# Schematic.net
KiCad netlist of a schematic drawn in Altium Designer
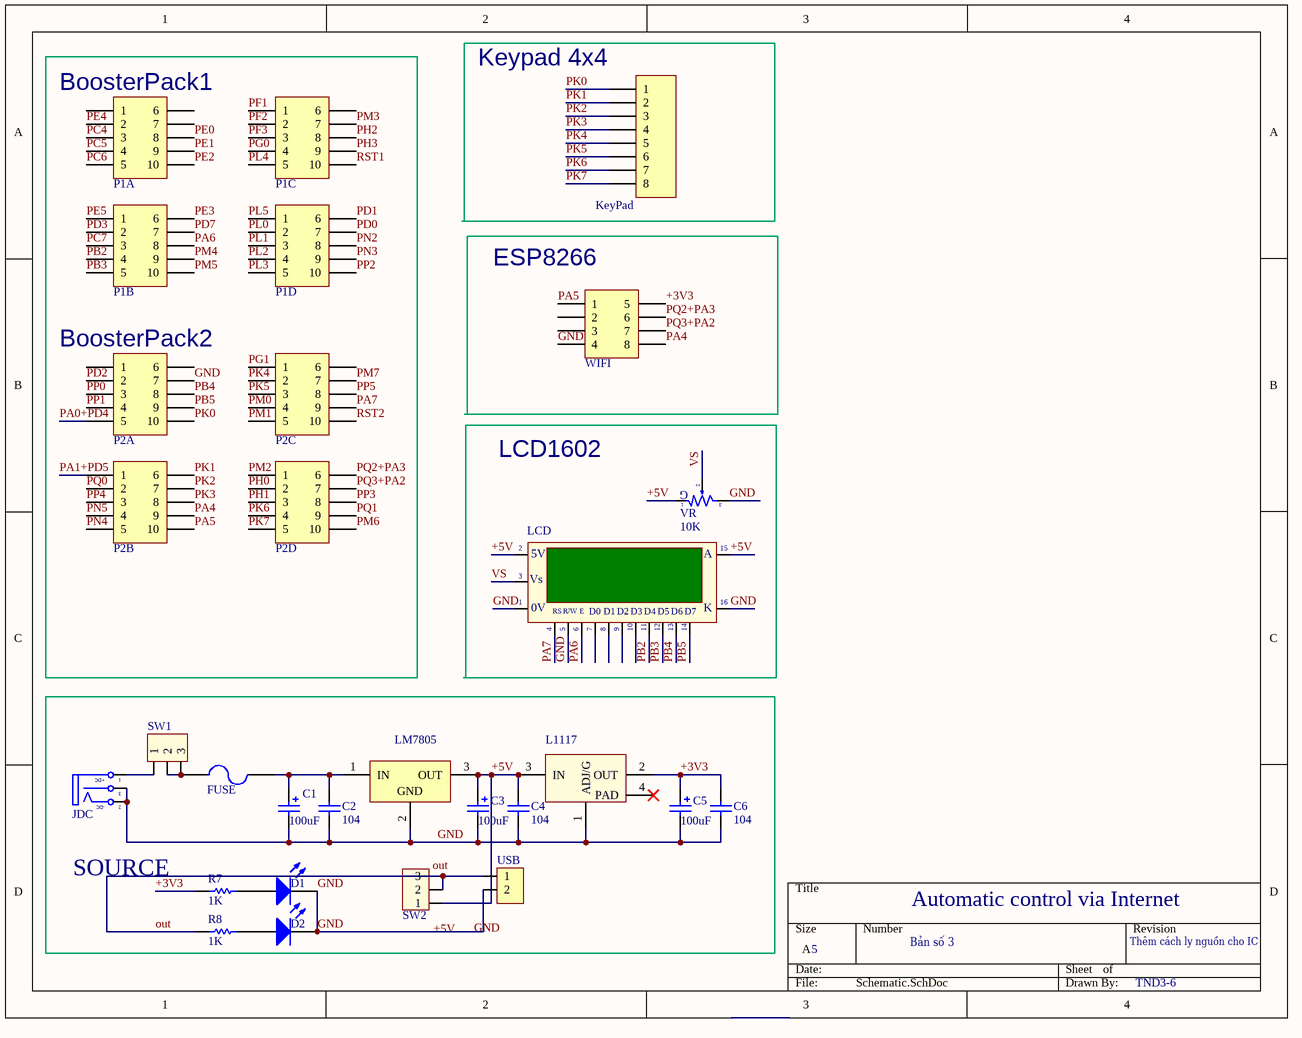
[diagram p0: Schematic.SchDoc]

(export (version "E")
  (design (tool "Eeschema 10.0.6"))
  (components
    (comp (ref "C1")
      (value "100uF")
      (footprint "CP1/2")
      (description "Polarized Capacitor (Radial)")
      (fields (field (name "Comment") "Cap Pol"))
      (libsource (lib "PIF_Library") (part "Cap Pol"))
    )
    (comp (ref "C2")
      (value "104")
      (footprint "CN1")
      (description "Capacitor")
      (fields (field (name "Comment") "Cap Non-Pol"))
      (libsource (lib "PIF_Library") (part "Cap Non-Pol"))
    )
    (comp (ref "C3")
      (value "100uF")
      (footprint "CP1/2")
      (description "Polarized Capacitor (Radial)")
      (fields (field (name "Comment") "Cap Pol"))
      (libsource (lib "PIF_Library") (part "Cap Pol"))
    )
    (comp (ref "C4")
      (value "104")
      (footprint "CN1")
      (description "Capacitor")
      (fields (field (name "Comment") "Cap Non-Pol"))
      (libsource (lib "PIF_Library") (part "Cap Non-Pol"))
    )
    (comp (ref "C5")
      (value "100uF")
      (footprint "CP1/2")
      (description "Polarized Capacitor (Radial)")
      (fields (field (name "Comment") "Cap Pol"))
      (libsource (lib "PIF_Library") (part "Cap Pol"))
    )
    (comp (ref "C6")
      (value "104")
      (footprint "CN1")
      (description "Capacitor")
      (fields (field (name "Comment") "Cap Non-Pol"))
      (libsource (lib "PIF_Library") (part "Cap Non-Pol"))
    )
    (comp (ref "D1") (value "LED") (footprint "LED-3mm") (libsource (lib "PIF_Library") (part "LED")))
    (comp (ref "D2") (value "LED") (footprint "LED-3mm") (libsource (lib "PIF_Library") (part "LED")))
    (comp (ref "FUSE") (value "Fuse") (footprint "FUSE") (libsource (lib "PIF_Library") (part "Fuse")))
    (comp (ref "JDC")
      (value "Jack DC")
      (footprint "DC-IN")
      (description "Jack DC input")
      (libsource (lib "PIF_Library") (part "Jack DC"))
    )
    (comp (ref "KeyPad")
      (value "Header 8")
      (footprint "JP8")
      (description "Header, 8-Pin")
      (fields (field (name "PUBLISHER") "Altium Limited"))
      (libsource (lib "PIF_Library") (part "Header 8"))
    )
    (comp (ref "L1117")
      (value "LM1117")
      (footprint "SOT223-4N")
      (description "Available in 1.8V, 2.5V, 2.85V, 3.3V, 5V, and  Adjustable Versions")
      (libsource (lib "PIF_Library") (part "LM1117"))
    )
    (comp (ref "LCD")
      (value "~")
      (footprint "LCD16X2")
      (description "LCD dipslay 16 char, 2 line")
      (libsource (lib "LIBRARY") (part "LCD16x2A"))
    )
    (comp (ref "LM7805")
      (value "LM7805")
      (footprint "QTO-220")
      (description "Positive Voltage Regulator")
      (libsource (lib "PIF_Library") (part "LM7805"))
    )
    (comp (ref "P1A")
      (value "Header 5X2")
      (footprint "JP5X2")
      (description "Header, 5-Pin, Dual row")
      (fields (field (name "PUBLISHER") "Altium Limited"))
      (libsource (lib "PIF_Library") (part "Header 5X2"))
    )
    (comp (ref "P1B")
      (value "Header 5X2")
      (footprint "JP5X2")
      (description "Header, 5-Pin, Dual row")
      (fields (field (name "PUBLISHER") "Altium Limited"))
      (libsource (lib "PIF_Library") (part "Header 5X2"))
    )
    (comp (ref "P1C")
      (value "Header 5X2")
      (footprint "JP5X2")
      (description "Header, 5-Pin, Dual row")
      (fields (field (name "PUBLISHER") "Altium Limited"))
      (libsource (lib "PIF_Library") (part "Header 5X2"))
    )
    (comp (ref "P1D")
      (value "Header 5X2")
      (footprint "JP5X2")
      (description "Header, 5-Pin, Dual row")
      (fields (field (name "PUBLISHER") "Altium Limited"))
      (libsource (lib "PIF_Library") (part "Header 5X2"))
    )
    (comp (ref "P2A")
      (value "Header 5X2")
      (footprint "JP5X2")
      (description "Header, 5-Pin, Dual row")
      (fields (field (name "PUBLISHER") "Altium Limited"))
      (libsource (lib "PIF_Library") (part "Header 5X2"))
    )
    (comp (ref "P2B")
      (value "Header 5X2")
      (footprint "JP5X2")
      (description "Header, 5-Pin, Dual row")
      (fields (field (name "PUBLISHER") "Altium Limited"))
      (libsource (lib "PIF_Library") (part "Header 5X2"))
    )
    (comp (ref "P2C")
      (value "Header 5X2")
      (footprint "JP5X2")
      (description "Header, 5-Pin, Dual row")
      (fields (field (name "PUBLISHER") "Altium Limited"))
      (libsource (lib "PIF_Library") (part "Header 5X2"))
    )
    (comp (ref "P2D")
      (value "Header 5X2")
      (footprint "JP5X2")
      (description "Header, 5-Pin, Dual row")
      (fields (field (name "PUBLISHER") "Altium Limited"))
      (libsource (lib "PIF_Library") (part "Header 5X2"))
    )
    (comp (ref "R7")
      (value "1K")
      (footprint "RES 1/2W")
      (description "Resistor")
      (fields (field (name "Comment") "RESISTOR"))
      (libsource (lib "PIF_Library") (part "RESISTOR"))
    )
    (comp (ref "R8")
      (value "1K")
      (footprint "RES 1/2W")
      (description "Resistor")
      (fields (field (name "Comment") "RESISTOR"))
      (libsource (lib "PIF_Library") (part "RESISTOR"))
    )
    (comp (ref "SW1")
      (value "~")
      (footprint "HED3")
      (description "Header 3 (Green)")
      (libsource (lib "syhaunguyen") (part "Hed3"))
    )
    (comp (ref "SW2")
      (value "~")
      (footprint "HED3")
      (description "Header 3 (Green)")
      (libsource (lib "") (part "Hed3_1"))
    )
    (comp (ref "USB")
      (value "~")
      (footprint "Header2")
      (description "Header IDC, 2 x 1 Pin Vertical 2.54mm Pitch (Non-Boxed, Male)")
      (fields
        (field (name "MANUFACTURER") "Würth Elektronik eiSos GmbH")
        (field (name "PARTNO") "613002143121")
        (field (name "CREATED BY") "Karrer Zheng")
      )
      (libsource (lib "LIBRARY") (part "Header2"))
    )
    (comp (ref "VR")
      (value "10K")
      (footprint "VR")
      (description "Var Resistor")
      (libsource (lib "LIBRARY") (part "VR-S"))
    )
    (comp (ref "WIFI")
      (value "Header 4X2")
      (footprint "JP4x2")
      (description "Header, 4-Pin, Dual row")
      (fields (field (name "PUBLISHER") "Altium Limited"))
      (libsource (lib "PIF_Library") (part "Header 4X2"))
    )
  )
  (nets
    (net (code "1") (name "/+3V3") (class "Default")
      (node (ref "C5") (pin "1") (pinfunction "1_1") (pintype "passive"))
      (node (ref "C6") (pin "2") (pinfunction "2_2") (pintype "passive"))
      (node (ref "L1117") (pin "2") (pinfunction "OUT_2") (pintype "passive"))
      (node (ref "R7") (pin "1") (pinfunction "1_1") (pintype "passive"))
      (node (ref "WIFI") (pin "5") (pinfunction "5_5") (pintype "passive"))
    )
    (net (code "2") (name "/+5V") (class "Default")
      (node (ref "C3") (pin "1") (pinfunction "1_1") (pintype "passive"))
      (node (ref "C4") (pin "2") (pinfunction "2_2") (pintype "passive"))
      (node (ref "L1117") (pin "3") (pinfunction "IN_3") (pintype "passive"))
      (node (ref "LCD") (pin "15") (pinfunction "A_15") (pintype "passive"))
      (node (ref "LCD") (pin "2") (pinfunction "VDD_2") (pintype "passive"))
      (node (ref "LM7805") (pin "3") (pinfunction "OUT_3") (pintype "power_in"))
      (node (ref "SW2") (pin "1") (pinfunction "1_1") (pintype "passive"))
      (node (ref "VR") (pin "1") (pinfunction "1_1") (pintype "passive"))
    )
    (net (code "3") (name "/GND") (class "Default")
      (node (ref "C1") (pin "2") (pinfunction "2_2") (pintype "passive"))
      (node (ref "C2") (pin "1") (pinfunction "1_1") (pintype "passive"))
      (node (ref "C3") (pin "2") (pinfunction "2_2") (pintype "passive"))
      (node (ref "C4") (pin "1") (pinfunction "1_1") (pintype "passive"))
      (node (ref "C5") (pin "2") (pinfunction "2_2") (pintype "passive"))
      (node (ref "C6") (pin "1") (pinfunction "1_1") (pintype "passive"))
      (node (ref "D1") (pin "2") (pinfunction "K_2") (pintype "passive"))
      (node (ref "D2") (pin "2") (pinfunction "K_2") (pintype "passive"))
      (node (ref "JDC") (pin "2") (pinfunction "TN_2") (pintype "passive"))
      (node (ref "JDC") (pin "3") (pinfunction "S_3") (pintype "power_in"))
      (node (ref "L1117") (pin "1") (pinfunction "ADJ/G_1") (pintype "passive"))
      (node (ref "LCD") (pin "1") (pinfunction "GND_1") (pintype "passive"))
      (node (ref "LCD") (pin "16") (pinfunction "K_16") (pintype "passive"))
      (node (ref "LCD") (pin "5") (pinfunction "R/~{W}_5") (pintype "passive"))
      (node (ref "LM7805") (pin "2") (pinfunction "GND_2") (pintype "power_in"))
      (node (ref "P2A") (pin "7") (pinfunction "7_7") (pintype "passive"))
      (node (ref "USB") (pin "2") (pinfunction "2_2") (pintype "passive"))
      (node (ref "VR") (pin "3") (pinfunction "3_3") (pintype "passive"))
      (node (ref "WIFI") (pin "4") (pinfunction "4_4") (pintype "passive"))
    )
    (net (code "4") (name "/PA0+PD4") (class "Default")
      (node (ref "P2A") (pin "5") (pinfunction "5_5") (pintype "passive"))
    )
    (net (code "5") (name "/PA1+PD5") (class "Default")
      (node (ref "P2B") (pin "1") (pinfunction "1_1") (pintype "passive"))
    )
    (net (code "6") (name "/PA4") (class "Default")
      (node (ref "P2B") (pin "9") (pinfunction "9_9") (pintype "passive"))
      (node (ref "WIFI") (pin "8") (pinfunction "8_8") (pintype "passive"))
    )
    (net (code "7") (name "/PA5") (class "Default")
      (node (ref "P2B") (pin "10") (pinfunction "10_10") (pintype "passive"))
      (node (ref "WIFI") (pin "1") (pinfunction "1_1") (pintype "passive"))
    )
    (net (code "8") (name "/PA6") (class "Default")
      (node (ref "LCD") (pin "6") (pinfunction "~{EN}_6") (pintype "passive"))
      (node (ref "P1B") (pin "8") (pinfunction "8_8") (pintype "passive"))
    )
    (net (code "9") (name "/PA7") (class "Default")
      (node (ref "LCD") (pin "4") (pinfunction "RS_4") (pintype "passive"))
      (node (ref "P2C") (pin "9") (pinfunction "9_9") (pintype "passive"))
    )
    (net (code "10") (name "/PB2") (class "Default")
      (node (ref "LCD") (pin "11") (pinfunction "D4_11") (pintype "passive"))
      (node (ref "P1B") (pin "4") (pinfunction "4_4") (pintype "passive"))
    )
    (net (code "11") (name "/PB3") (class "Default")
      (node (ref "LCD") (pin "12") (pinfunction "D5_12") (pintype "passive"))
      (node (ref "P1B") (pin "5") (pinfunction "5_5") (pintype "passive"))
    )
    (net (code "12") (name "/PB4") (class "Default")
      (node (ref "LCD") (pin "13") (pinfunction "D6_13") (pintype "passive"))
      (node (ref "P2A") (pin "8") (pinfunction "8_8") (pintype "passive"))
    )
    (net (code "13") (name "/PB5") (class "Default")
      (node (ref "LCD") (pin "14") (pinfunction "D7_14") (pintype "passive"))
      (node (ref "P2A") (pin "9") (pinfunction "9_9") (pintype "passive"))
    )
    (net (code "14") (name "/PC4") (class "Default")
      (node (ref "P1A") (pin "3") (pinfunction "3_3") (pintype "passive"))
    )
    (net (code "15") (name "/PC5") (class "Default")
      (node (ref "P1A") (pin "4") (pinfunction "4_4") (pintype "passive"))
    )
    (net (code "16") (name "/PC6") (class "Default")
      (node (ref "P1A") (pin "5") (pinfunction "5_5") (pintype "passive"))
    )
    (net (code "17") (name "/PC7") (class "Default")
      (node (ref "P1B") (pin "3") (pinfunction "3_3") (pintype "passive"))
    )
    (net (code "18") (name "/PD0") (class "Default")
      (node (ref "P1D") (pin "7") (pinfunction "7_7") (pintype "passive"))
    )
    (net (code "19") (name "/PD1") (class "Default")
      (node (ref "P1D") (pin "6") (pinfunction "6_6") (pintype "passive"))
    )
    (net (code "20") (name "/PD2") (class "Default")
      (node (ref "P2A") (pin "2") (pinfunction "2_2") (pintype "passive"))
    )
    (net (code "21") (name "/PD3") (class "Default")
      (node (ref "P1B") (pin "2") (pinfunction "2_2") (pintype "passive"))
    )
    (net (code "22") (name "/PD7") (class "Default")
      (node (ref "P1B") (pin "7") (pinfunction "7_7") (pintype "passive"))
    )
    (net (code "23") (name "/PE0") (class "Default")
      (node (ref "P1A") (pin "8") (pinfunction "8_8") (pintype "passive"))
    )
    (net (code "24") (name "/PE1") (class "Default")
      (node (ref "P1A") (pin "9") (pinfunction "9_9") (pintype "passive"))
    )
    (net (code "25") (name "/PE2") (class "Default")
      (node (ref "P1A") (pin "10") (pinfunction "10_10") (pintype "passive"))
    )
    (net (code "26") (name "/PE3") (class "Default")
      (node (ref "P1B") (pin "6") (pinfunction "6_6") (pintype "passive"))
    )
    (net (code "27") (name "/PE4") (class "Default")
      (node (ref "P1A") (pin "2") (pinfunction "2_2") (pintype "passive"))
    )
    (net (code "28") (name "/PE5") (class "Default")
      (node (ref "P1B") (pin "1") (pinfunction "1_1") (pintype "passive"))
    )
    (net (code "29") (name "/PF1") (class "Default")
      (node (ref "P1C") (pin "1") (pinfunction "1_1") (pintype "passive"))
    )
    (net (code "30") (name "/PF2") (class "Default")
      (node (ref "P1C") (pin "2") (pinfunction "2_2") (pintype "passive"))
    )
    (net (code "31") (name "/PF3") (class "Default")
      (node (ref "P1C") (pin "3") (pinfunction "3_3") (pintype "passive"))
    )
    (net (code "32") (name "/PG0") (class "Default")
      (node (ref "P1C") (pin "4") (pinfunction "4_4") (pintype "passive"))
    )
    (net (code "33") (name "/PG1") (class "Default")
      (node (ref "P2C") (pin "1") (pinfunction "1_1") (pintype "passive"))
    )
    (net (code "34") (name "/PH0") (class "Default")
      (node (ref "P2D") (pin "2") (pinfunction "2_2") (pintype "passive"))
    )
    (net (code "35") (name "/PH1") (class "Default")
      (node (ref "P2D") (pin "3") (pinfunction "3_3") (pintype "passive"))
    )
    (net (code "36") (name "/PH2") (class "Default")
      (node (ref "P1C") (pin "8") (pinfunction "8_8") (pintype "passive"))
    )
    (net (code "37") (name "/PH3") (class "Default")
      (node (ref "P1C") (pin "9") (pinfunction "9_9") (pintype "passive"))
    )
    (net (code "38") (name "/PK0") (class "Default")
      (node (ref "KeyPad") (pin "1") (pinfunction "1_1") (pintype "passive"))
      (node (ref "P2A") (pin "10") (pinfunction "10_10") (pintype "passive"))
    )
    (net (code "39") (name "/PK1") (class "Default")
      (node (ref "KeyPad") (pin "2") (pinfunction "2_2") (pintype "passive"))
      (node (ref "P2B") (pin "6") (pinfunction "6_6") (pintype "passive"))
    )
    (net (code "40") (name "/PK2") (class "Default")
      (node (ref "KeyPad") (pin "3") (pinfunction "3_3") (pintype "passive"))
      (node (ref "P2B") (pin "7") (pinfunction "7_7") (pintype "passive"))
    )
    (net (code "41") (name "/PK3") (class "Default")
      (node (ref "KeyPad") (pin "4") (pinfunction "4_4") (pintype "passive"))
      (node (ref "P2B") (pin "8") (pinfunction "8_8") (pintype "passive"))
    )
    (net (code "42") (name "/PK4") (class "Default")
      (node (ref "KeyPad") (pin "5") (pinfunction "5_5") (pintype "passive"))
      (node (ref "P2C") (pin "2") (pinfunction "2_2") (pintype "passive"))
    )
    (net (code "43") (name "/PK5") (class "Default")
      (node (ref "KeyPad") (pin "6") (pinfunction "6_6") (pintype "passive"))
      (node (ref "P2C") (pin "3") (pinfunction "3_3") (pintype "passive"))
    )
    (net (code "44") (name "/PK6") (class "Default")
      (node (ref "KeyPad") (pin "7") (pinfunction "7_7") (pintype "passive"))
      (node (ref "P2D") (pin "4") (pinfunction "4_4") (pintype "passive"))
    )
    (net (code "45") (name "/PK7") (class "Default")
      (node (ref "KeyPad") (pin "8") (pinfunction "8_8") (pintype "passive"))
      (node (ref "P2D") (pin "5") (pinfunction "5_5") (pintype "passive"))
    )
    (net (code "46") (name "/PL0") (class "Default")
      (node (ref "P1D") (pin "2") (pinfunction "2_2") (pintype "passive"))
    )
    (net (code "47") (name "/PL1") (class "Default")
      (node (ref "P1D") (pin "3") (pinfunction "3_3") (pintype "passive"))
    )
    (net (code "48") (name "/PL2") (class "Default")
      (node (ref "P1D") (pin "4") (pinfunction "4_4") (pintype "passive"))
    )
    (net (code "49") (name "/PL3") (class "Default")
      (node (ref "P1D") (pin "5") (pinfunction "5_5") (pintype "passive"))
    )
    (net (code "50") (name "/PL4") (class "Default")
      (node (ref "P1C") (pin "5") (pinfunction "5_5") (pintype "passive"))
    )
    (net (code "51") (name "/PL5") (class "Default")
      (node (ref "P1D") (pin "1") (pinfunction "1_1") (pintype "passive"))
    )
    (net (code "52") (name "/PM0") (class "Default")
      (node (ref "P2C") (pin "4") (pinfunction "4_4") (pintype "passive"))
    )
    (net (code "53") (name "/PM1") (class "Default")
      (node (ref "P2C") (pin "5") (pinfunction "5_5") (pintype "passive"))
    )
    (net (code "54") (name "/PM2") (class "Default")
      (node (ref "P2D") (pin "1") (pinfunction "1_1") (pintype "passive"))
    )
    (net (code "55") (name "/PM3") (class "Default")
      (node (ref "P1C") (pin "7") (pinfunction "7_7") (pintype "passive"))
    )
    (net (code "56") (name "/PM4") (class "Default")
      (node (ref "P1B") (pin "9") (pinfunction "9_9") (pintype "passive"))
    )
    (net (code "57") (name "/PM5") (class "Default")
      (node (ref "P1B") (pin "10") (pinfunction "10_10") (pintype "passive"))
    )
    (net (code "58") (name "/PM6") (class "Default")
      (node (ref "P2D") (pin "10") (pinfunction "10_10") (pintype "passive"))
    )
    (net (code "59") (name "/PM7") (class "Default")
      (node (ref "P2C") (pin "7") (pinfunction "7_7") (pintype "passive"))
    )
    (net (code "60") (name "/PN2") (class "Default")
      (node (ref "P1D") (pin "8") (pinfunction "8_8") (pintype "passive"))
    )
    (net (code "61") (name "/PN3") (class "Default")
      (node (ref "P1D") (pin "9") (pinfunction "9_9") (pintype "passive"))
    )
    (net (code "62") (name "/PN4") (class "Default")
      (node (ref "P2B") (pin "5") (pinfunction "5_5") (pintype "passive"))
    )
    (net (code "63") (name "/PN5") (class "Default")
      (node (ref "P2B") (pin "4") (pinfunction "4_4") (pintype "passive"))
    )
    (net (code "64") (name "/PP0") (class "Default")
      (node (ref "P2A") (pin "3") (pinfunction "3_3") (pintype "passive"))
    )
    (net (code "65") (name "/PP1") (class "Default")
      (node (ref "P2A") (pin "4") (pinfunction "4_4") (pintype "passive"))
    )
    (net (code "66") (name "/PP2") (class "Default")
      (node (ref "P1D") (pin "10") (pinfunction "10_10") (pintype "passive"))
    )
    (net (code "67") (name "/PP3") (class "Default")
      (node (ref "P2D") (pin "8") (pinfunction "8_8") (pintype "passive"))
    )
    (net (code "68") (name "/PP4") (class "Default")
      (node (ref "P2B") (pin "3") (pinfunction "3_3") (pintype "passive"))
    )
    (net (code "69") (name "/PP5") (class "Default")
      (node (ref "P2C") (pin "8") (pinfunction "8_8") (pintype "passive"))
    )
    (net (code "70") (name "/PQ0") (class "Default")
      (node (ref "P2B") (pin "2") (pinfunction "2_2") (pintype "passive"))
    )
    (net (code "71") (name "/PQ1") (class "Default")
      (node (ref "P2D") (pin "9") (pinfunction "9_9") (pintype "passive"))
    )
    (net (code "72") (name "/PQ2+PA3") (class "Default")
      (node (ref "P2D") (pin "6") (pinfunction "6_6") (pintype "passive"))
      (node (ref "WIFI") (pin "6") (pinfunction "6_6") (pintype "passive"))
    )
    (net (code "73") (name "/PQ3+PA2") (class "Default")
      (node (ref "P2D") (pin "7") (pinfunction "7_7") (pintype "passive"))
      (node (ref "WIFI") (pin "7") (pinfunction "7_7") (pintype "passive"))
    )
    (net (code "74") (name "/RST1") (class "Default")
      (node (ref "P1C") (pin "10") (pinfunction "10_10") (pintype "passive"))
    )
    (net (code "75") (name "/RST2") (class "Default")
      (node (ref "P2C") (pin "10") (pinfunction "10_10") (pintype "passive"))
    )
    (net (code "76") (name "/VS") (class "Default")
      (node (ref "LCD") (pin "3") (pinfunction "VEE_3") (pintype "passive"))
      (node (ref "VR") (pin "2") (pinfunction "2_2") (pintype "passive"))
    )
    (net (code "77") (name "/out") (class "Default")
      (node (ref "R8") (pin "1") (pinfunction "1_1") (pintype "passive"))
      (node (ref "SW2") (pin "2") (pinfunction "2_2") (pintype "passive"))
      (node (ref "SW2") (pin "3") (pinfunction "3_3") (pintype "passive"))
      (node (ref "USB") (pin "1") (pinfunction "1_1") (pintype "passive"))
    )
    (net (code "78") (name "Net-(D1-A)") (class "Default")
      (node (ref "D1") (pin "1") (pinfunction "A_1") (pintype "passive"))
      (node (ref "R7") (pin "2") (pinfunction "2_2") (pintype "passive"))
    )
    (net (code "79") (name "Net-(D2-A)") (class "Default")
      (node (ref "D2") (pin "1") (pinfunction "A_1") (pintype "passive"))
      (node (ref "R8") (pin "2") (pinfunction "2_2") (pintype "passive"))
    )
    (net (code "80") (name "Net-(FUSE-Pad1)") (class "Default")
      (node (ref "FUSE") (pin "1") (pinfunction "1_1") (pintype "passive"))
      (node (ref "SW1") (pin "2") (pinfunction "2_2") (pintype "passive"))
      (node (ref "SW1") (pin "3") (pinfunction "3_3") (pintype "passive"))
    )
    (net (code "81") (name "Net-(JDC-T)") (class "Default")
      (node (ref "JDC") (pin "1") (pinfunction "T_1") (pintype "passive"))
      (node (ref "SW1") (pin "1") (pinfunction "1_1") (pintype "passive"))
    )
    (net (code "82") (name "Net-(LM7805-IN)") (class "Default")
      (node (ref "C1") (pin "1") (pinfunction "1_1") (pintype "passive"))
      (node (ref "C2") (pin "2") (pinfunction "2_2") (pintype "passive"))
      (node (ref "FUSE") (pin "2") (pinfunction "2_2") (pintype "passive"))
      (node (ref "LM7805") (pin "1") (pinfunction "IN_1") (pintype "power_in"))
    )
    (net (code "83") (name "unconnected-(L1117-PAD-Pad4)") (class "Default")
      (node (ref "L1117") (pin "4") (pinfunction "PAD_4") (pintype "passive+no_connect"))
    )
    (net (code "84") (name "unconnected-(LCD-D0-Pad7)") (class "Default")
      (node (ref "LCD") (pin "7") (pinfunction "D0_7") (pintype "passive"))
    )
    (net (code "85") (name "unconnected-(LCD-D1-Pad8)") (class "Default")
      (node (ref "LCD") (pin "8") (pinfunction "D1_8") (pintype "passive"))
    )
    (net (code "86") (name "unconnected-(LCD-D2-Pad9)") (class "Default")
      (node (ref "LCD") (pin "9") (pinfunction "D2_9") (pintype "passive"))
    )
    (net (code "87") (name "unconnected-(LCD-D3-Pad10)") (class "Default")
      (node (ref "LCD") (pin "10") (pinfunction "D3_10") (pintype "passive"))
    )
    (net (code "88") (name "unconnected-(P1A-Pad1)") (class "Default")
      (node (ref "P1A") (pin "1") (pinfunction "1_1") (pintype "passive"))
    )
    (net (code "89") (name "unconnected-(P1A-Pad6)") (class "Default")
      (node (ref "P1A") (pin "6") (pinfunction "6_6") (pintype "passive"))
    )
    (net (code "90") (name "unconnected-(P1A-Pad7)") (class "Default")
      (node (ref "P1A") (pin "7") (pinfunction "7_7") (pintype "passive"))
    )
    (net (code "91") (name "unconnected-(P1C-Pad6)") (class "Default")
      (node (ref "P1C") (pin "6") (pinfunction "6_6") (pintype "passive"))
    )
    (net (code "92") (name "unconnected-(P2A-Pad1)") (class "Default")
      (node (ref "P2A") (pin "1") (pinfunction "1_1") (pintype "passive"))
    )
    (net (code "93") (name "unconnected-(P2A-Pad6)") (class "Default")
      (node (ref "P2A") (pin "6") (pinfunction "6_6") (pintype "passive"))
    )
    (net (code "94") (name "unconnected-(P2C-Pad6)") (class "Default")
      (node (ref "P2C") (pin "6") (pinfunction "6_6") (pintype "passive"))
    )
    (net (code "95") (name "unconnected-(WIFI-Pad2)") (class "Default")
      (node (ref "WIFI") (pin "2") (pinfunction "2_2") (pintype "passive"))
    )
    (net (code "96") (name "unconnected-(WIFI-Pad3)") (class "Default")
      (node (ref "WIFI") (pin "3") (pinfunction "3_3") (pintype "passive"))
    )
  )
)
